# 468323_001_INT.net
KiCad netlist of a schematic drawn in Altium Designer
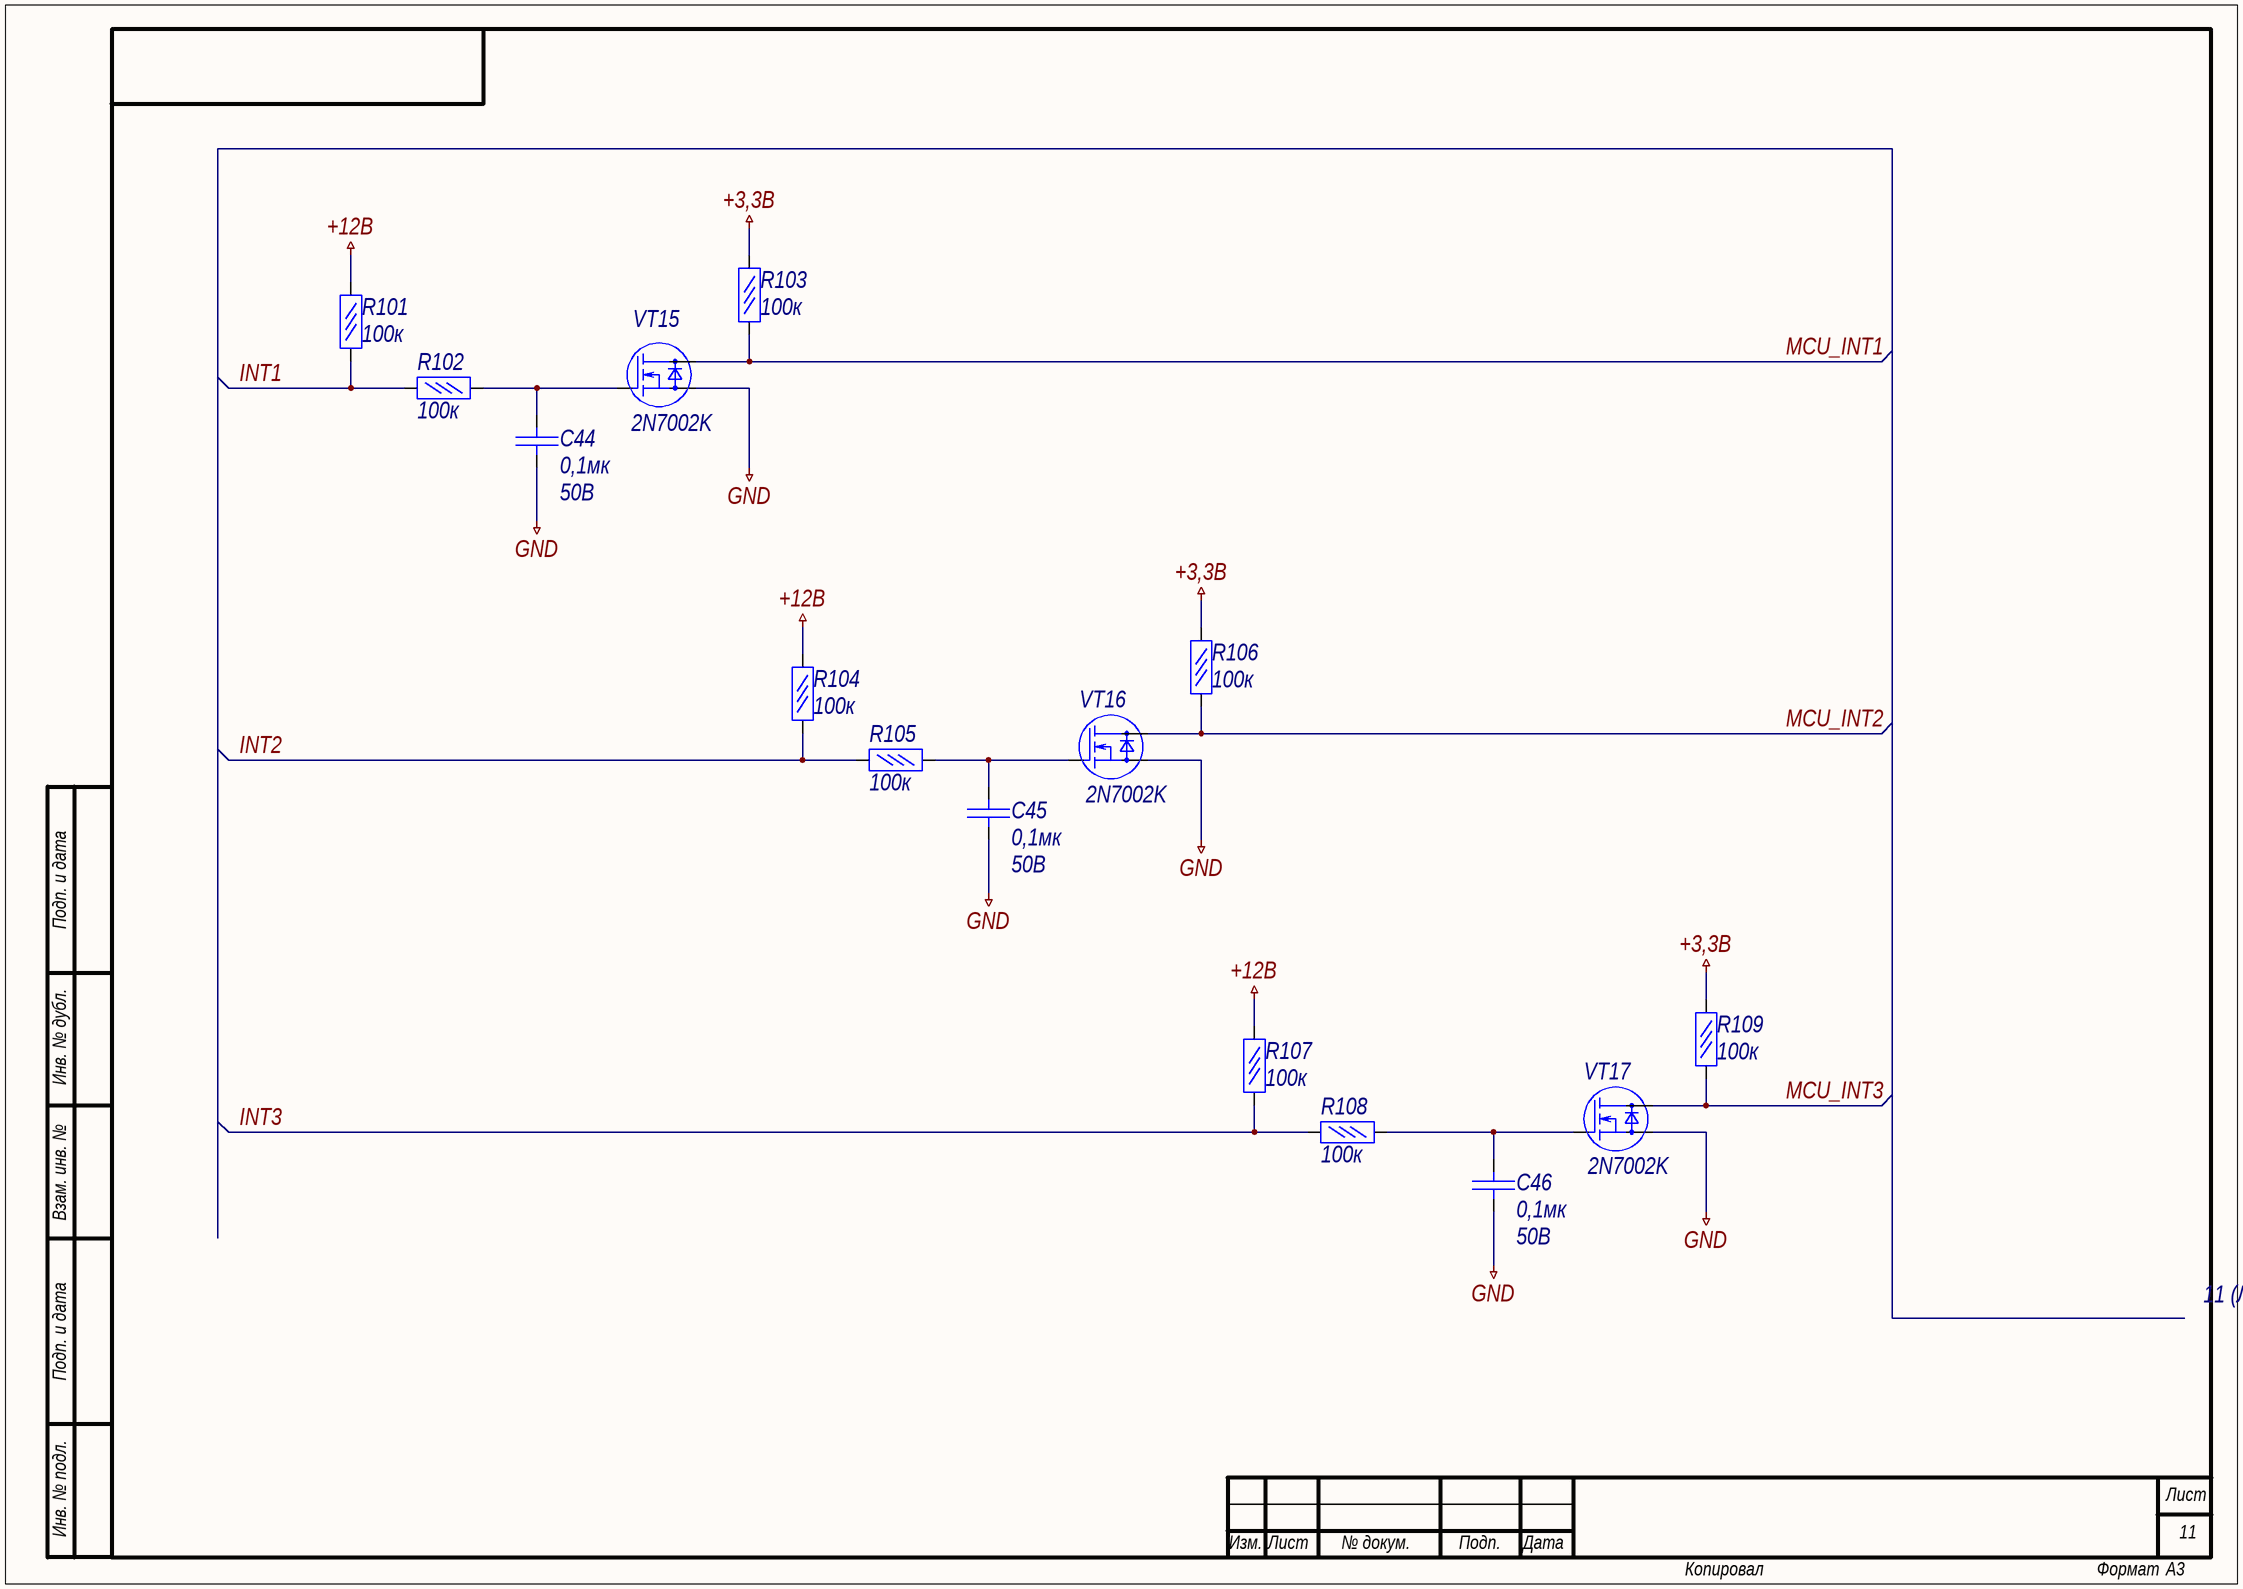
[diagram p0: РЕУН.468323.001_INT.SchDoc]

(export (version "E")
  (design (tool "Eeschema 10.0.6"))
  (components
    (comp (ref "C44")
      (value "0,1мк")
      (footprint "C0805_AA")
      (description "Конденсатор кер.")
      (fields (field (name "VOLTAGE") "50В"))
      (libsource (lib "Library_Diana") (part "Конденсатор кер."))
    )
    (comp (ref "C45")
      (value "0,1мк")
      (footprint "C0805_AA")
      (description "Конденсатор кер.")
      (fields (field (name "VOLTAGE") "50В"))
      (libsource (lib "Library_Diana") (part "Конденсатор кер."))
    )
    (comp (ref "C46")
      (value "0,1мк")
      (footprint "C0805_AA")
      (description "Конденсатор кер.")
      (fields (field (name "VOLTAGE") "50В"))
      (libsource (lib "Library_Diana") (part "Конденсатор кер."))
    )
    (comp (ref "R101")
      (value "100к")
      (footprint "R1206")
      (description "Резистор 0,05Вт")
      (libsource (lib "Library_Diana") (part "Резистор  0,05Вт"))
    )
    (comp (ref "R102")
      (value "100к")
      (footprint "R1206")
      (description "Резистор 0,05Вт")
      (libsource (lib "") (part "Резистор  0,05Вт_1"))
    )
    (comp (ref "R103")
      (value "100к")
      (footprint "R1206")
      (description "Резистор 0,05Вт")
      (libsource (lib "Library_Diana") (part "Резистор  0,05Вт"))
    )
    (comp (ref "R104")
      (value "100к")
      (footprint "R1206")
      (description "Резистор 0,05Вт")
      (libsource (lib "Library_Diana") (part "Резистор  0,05Вт"))
    )
    (comp (ref "R105")
      (value "100к")
      (footprint "R1206")
      (description "Резистор 0,05Вт")
      (libsource (lib "") (part "Резистор  0,05Вт_1"))
    )
    (comp (ref "R106")
      (value "100к")
      (footprint "R1206")
      (description "Резистор 0,05Вт")
      (libsource (lib "Library_Diana") (part "Резистор  0,05Вт"))
    )
    (comp (ref "R107")
      (value "100к")
      (footprint "R1206")
      (description "Резистор 0,05Вт")
      (libsource (lib "Library_Diana") (part "Резистор  0,05Вт"))
    )
    (comp (ref "R108")
      (value "100к")
      (footprint "R1206")
      (description "Резистор 0,05Вт")
      (libsource (lib "") (part "Резистор  0,05Вт_1"))
    )
    (comp (ref "R109")
      (value "100к")
      (footprint "R1206")
      (description "Резистор 0,05Вт")
      (libsource (lib "Library_Diana") (part "Резистор  0,05Вт"))
    )
    (comp (ref "VT15")
      (value "2N7002K")
      (footprint "SOT:SOT23-3")
      (fields (field (name "NAME") "2N7002K"))
      (libsource (lib "Library_Diana") (part "mosfet-n"))
    )
    (comp (ref "VT16")
      (value "2N7002K")
      (footprint "SOT:SOT23-3")
      (fields (field (name "NAME") "2N7002K"))
      (libsource (lib "Library_Diana") (part "mosfet-n"))
    )
    (comp (ref "VT17")
      (value "2N7002K")
      (footprint "SOT:SOT23-3")
      (fields (field (name "NAME") "2N7002K"))
      (libsource (lib "Library_Diana") (part "mosfet-n"))
    )
  )
  (nets
    (net (code "1") (name "+3,3В") (class "Default")
      (node (ref "R103") (pin "2") (pinfunction "2_2") (pintype "passive"))
      (node (ref "R106") (pin "2") (pinfunction "2_2") (pintype "passive"))
      (node (ref "R109") (pin "2") (pinfunction "2_2") (pintype "passive"))
    )
    (net (code "2") (name "+12В") (class "Default")
      (node (ref "R101") (pin "2") (pinfunction "2_2") (pintype "passive"))
      (node (ref "R104") (pin "2") (pinfunction "2_2") (pintype "passive"))
      (node (ref "R107") (pin "2") (pinfunction "2_2") (pintype "passive"))
    )
    (net (code "3") (name "/INT1") (class "Default")
      (node (ref "R101") (pin "1") (pinfunction "1_1") (pintype "passive"))
      (node (ref "R102") (pin "1") (pinfunction "1_1") (pintype "passive"))
    )
    (net (code "4") (name "/INT2") (class "Default")
      (node (ref "R104") (pin "1") (pinfunction "1_1") (pintype "passive"))
      (node (ref "R105") (pin "1") (pinfunction "1_1") (pintype "passive"))
    )
    (net (code "5") (name "/INT3") (class "Default")
      (node (ref "R107") (pin "1") (pinfunction "1_1") (pintype "passive"))
      (node (ref "R108") (pin "1") (pinfunction "1_1") (pintype "passive"))
    )
    (net (code "6") (name "/MCU_INT1") (class "Default")
      (node (ref "R103") (pin "1") (pinfunction "1_1") (pintype "passive"))
      (node (ref "VT15") (pin "3") (pinfunction "D_3") (pintype "passive"))
    )
    (net (code "7") (name "/MCU_INT2") (class "Default")
      (node (ref "R106") (pin "1") (pinfunction "1_1") (pintype "passive"))
      (node (ref "VT16") (pin "3") (pinfunction "D_3") (pintype "passive"))
    )
    (net (code "8") (name "/MCU_INT3") (class "Default")
      (node (ref "R109") (pin "1") (pinfunction "1_1") (pintype "passive"))
      (node (ref "VT17") (pin "3") (pinfunction "D_3") (pintype "passive"))
    )
    (net (code "9") (name "GND") (class "Default")
      (node (ref "C44") (pin "1") (pinfunction "1_1") (pintype "passive"))
      (node (ref "C45") (pin "1") (pinfunction "1_1") (pintype "passive"))
      (node (ref "C46") (pin "1") (pinfunction "1_1") (pintype "passive"))
      (node (ref "VT15") (pin "2") (pinfunction "S_2") (pintype "passive"))
      (node (ref "VT16") (pin "2") (pinfunction "S_2") (pintype "passive"))
      (node (ref "VT17") (pin "2") (pinfunction "S_2") (pintype "passive"))
    )
    (net (code "10") (name "Net-(VT15-G)") (class "Default")
      (node (ref "C44") (pin "2") (pinfunction "2_2") (pintype "passive"))
      (node (ref "R102") (pin "2") (pinfunction "2_2") (pintype "passive"))
      (node (ref "VT15") (pin "1") (pinfunction "G_1") (pintype "passive"))
    )
    (net (code "11") (name "Net-(VT16-G)") (class "Default")
      (node (ref "C45") (pin "2") (pinfunction "2_2") (pintype "passive"))
      (node (ref "R105") (pin "2") (pinfunction "2_2") (pintype "passive"))
      (node (ref "VT16") (pin "1") (pinfunction "G_1") (pintype "passive"))
    )
    (net (code "12") (name "Net-(VT17-G)") (class "Default")
      (node (ref "C46") (pin "2") (pinfunction "2_2") (pintype "passive"))
      (node (ref "R108") (pin "2") (pinfunction "2_2") (pintype "passive"))
      (node (ref "VT17") (pin "1") (pinfunction "G_1") (pintype "passive"))
    )
  )
)
